# boiler.net
KiCad netlist of a schematic drawn in EAGLE
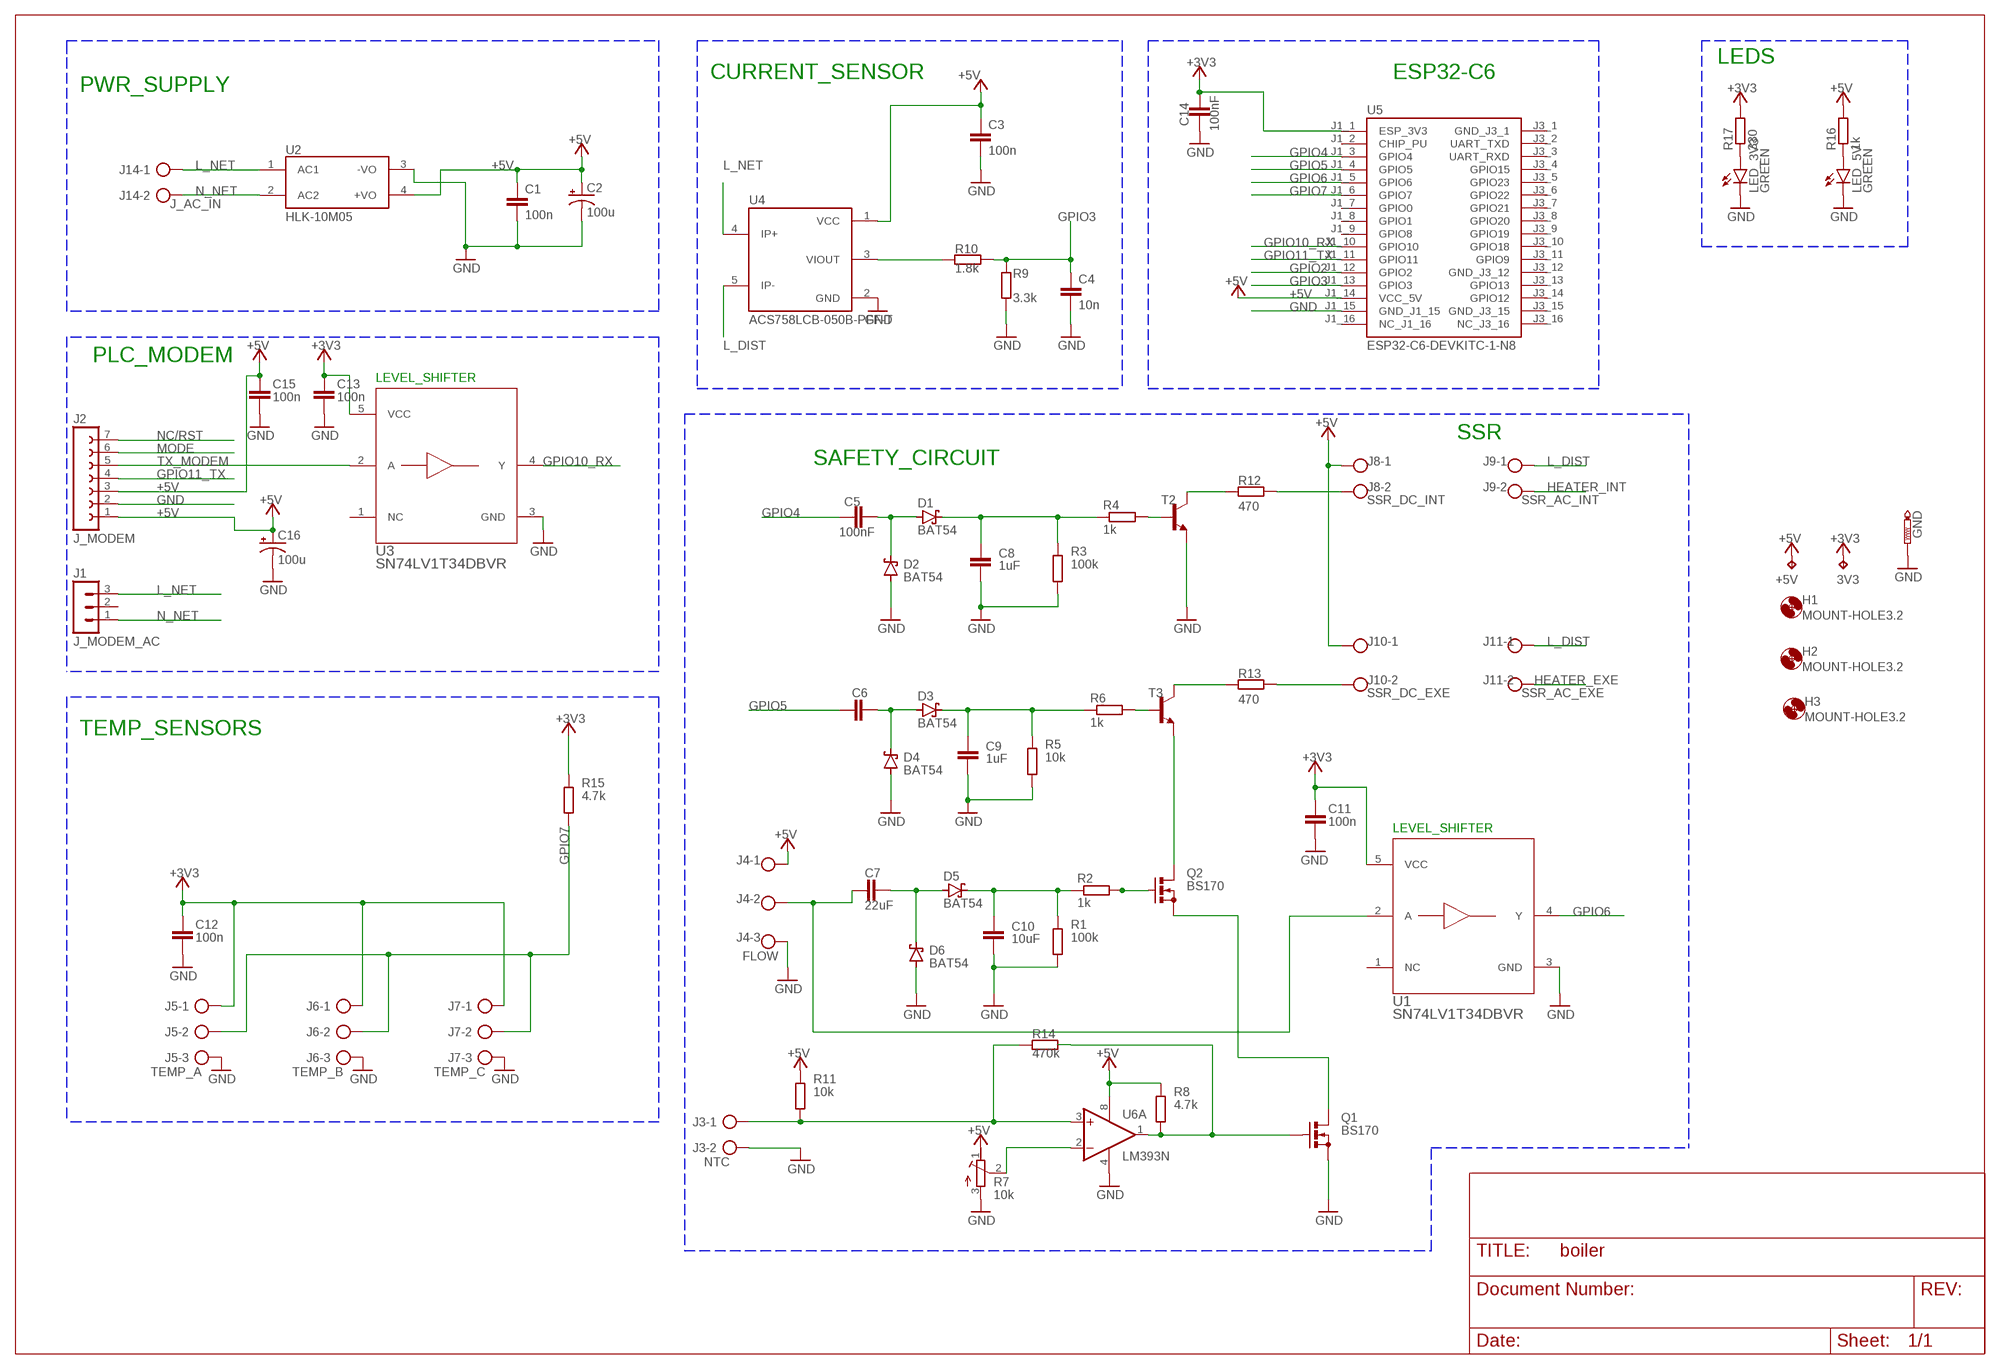
[diagram p0: schematic, sheet 1]

(export (version "E")
  (design (tool "Eeschema 10.0.6"))
  (components
    (comp (ref "+5V")
      (value "TPB2,54")
      (footprint "eagle-import:B2,54")
      (libsource (lib "eagle-import") (part "TPB2,54"))
    )
    (comp (ref "3V3")
      (value "TPB2,54")
      (footprint "eagle-import:B2,54")
      (libsource (lib "eagle-import") (part "TPB2,54"))
    )
    (comp (ref "C1")
      (value "100n")
      (footprint "eagle-import:C0603")
      (libsource (lib "eagle-import") (part "C-EUC0603"))
    )
    (comp (ref "C2")
      (value "100u")
      (footprint "eagle-import:PANASONIC_C")
      (libsource (lib "eagle-import") (part "CPOL-USC"))
    )
    (comp (ref "C3")
      (value "100n")
      (footprint "eagle-import:C0603")
      (libsource (lib "eagle-import") (part "C-EUC0603"))
    )
    (comp (ref "C4")
      (value "10n")
      (footprint "eagle-import:C0603")
      (libsource (lib "eagle-import") (part "C-EUC0603"))
    )
    (comp (ref "C5")
      (value "100nF")
      (footprint "eagle-import:C0603")
      (libsource (lib "eagle-import") (part "C-EUC0603"))
    )
    (comp (ref "C6")
      (value "1u")
      (footprint "eagle-import:C0603")
      (libsource (lib "eagle-import") (part "C-EUC0603"))
    )
    (comp (ref "C7")
      (value "22uF")
      (footprint "eagle-import:C0603")
      (libsource (lib "eagle-import") (part "C-EUC0603"))
    )
    (comp (ref "C8")
      (value "1uF")
      (footprint "eagle-import:C0603")
      (libsource (lib "eagle-import") (part "C-EUC0603"))
    )
    (comp (ref "C9")
      (value "1uF")
      (footprint "eagle-import:C0603")
      (libsource (lib "eagle-import") (part "C-EUC0603"))
    )
    (comp (ref "C10")
      (value "10uF")
      (footprint "eagle-import:C0603")
      (libsource (lib "eagle-import") (part "C-EUC0603"))
    )
    (comp (ref "C11")
      (value "100n")
      (footprint "eagle-import:C0603")
      (libsource (lib "eagle-import") (part "C-EUC0603"))
    )
    (comp (ref "C12")
      (value "100n")
      (footprint "eagle-import:C0603")
      (libsource (lib "eagle-import") (part "C-EUC0603"))
    )
    (comp (ref "C13")
      (value "100n")
      (footprint "eagle-import:C0603")
      (libsource (lib "eagle-import") (part "C-EUC0603"))
    )
    (comp (ref "C14")
      (value "100nF")
      (footprint "eagle-import:C0603")
      (libsource (lib "eagle-import") (part "C-EUC0603"))
    )
    (comp (ref "C15")
      (value "100n")
      (footprint "eagle-import:C0603")
      (libsource (lib "eagle-import") (part "C-EUC0603"))
    )
    (comp (ref "C16")
      (value "100u")
      (footprint "eagle-import:PANASONIC_C")
      (libsource (lib "eagle-import") (part "CPOL-USC"))
    )
    (comp (ref "D1")
      (value "BAT54")
      (footprint "eagle-import:SOT23")
      (libsource (lib "eagle-import") (part "BAT54"))
    )
    (comp (ref "D2")
      (value "BAT54")
      (footprint "eagle-import:SOT23")
      (libsource (lib "eagle-import") (part "BAT54"))
    )
    (comp (ref "D3")
      (value "BAT54")
      (footprint "eagle-import:SOT23")
      (libsource (lib "eagle-import") (part "BAT54"))
    )
    (comp (ref "D4")
      (value "BAT54")
      (footprint "eagle-import:SOT23")
      (libsource (lib "eagle-import") (part "BAT54"))
    )
    (comp (ref "D5")
      (value "BAT54")
      (footprint "eagle-import:SOT23")
      (libsource (lib "eagle-import") (part "BAT54"))
    )
    (comp (ref "D6")
      (value "BAT54")
      (footprint "eagle-import:SOT23")
      (libsource (lib "eagle-import") (part "BAT54"))
    )
    (comp (ref "GND")
      (value "PTR1TP15R")
      (footprint "eagle-import:TP15R")
      (libsource (lib "eagle-import") (part "PTR1TP15R"))
    )
    (comp (ref "H1")
      (value "MOUNT-HOLE3.2")
      (footprint "eagle-import:3,2")
      (libsource (lib "eagle-import") (part "MOUNT-HOLE3.2"))
    )
    (comp (ref "H2")
      (value "MOUNT-HOLE3.2")
      (footprint "eagle-import:3,2")
      (libsource (lib "eagle-import") (part "MOUNT-HOLE3.2"))
    )
    (comp (ref "H3")
      (value "MOUNT-HOLE3.2")
      (footprint "eagle-import:3,2")
      (libsource (lib "eagle-import") (part "MOUNT-HOLE3.2"))
    )
    (comp (ref "J1")
      (value "J_MODEM_AC")
      (footprint "eagle-import:MA03-1")
      (libsource (lib "eagle-import") (part "MA03-1"))
    )
    (comp (ref "J2")
      (value "J_MODEM")
      (footprint "eagle-import:FE07")
      (libsource (lib "eagle-import") (part "FE07-1"))
    )
    (comp (ref "J3")
      (value "NTC")
      (footprint "eagle-import:AK500_2")
      (libsource (lib "eagle-import") (part "AK500/2"))
    )
    (comp (ref "J4")
      (value "FLOW")
      (footprint "eagle-import:AK500_3")
      (libsource (lib "eagle-import") (part "AK500/3"))
    )
    (comp (ref "J5")
      (value "TEMP_A")
      (footprint "eagle-import:AK500_3")
      (libsource (lib "eagle-import") (part "AK500/3"))
    )
    (comp (ref "J6")
      (value "TEMP_B")
      (footprint "eagle-import:AK500_3")
      (libsource (lib "eagle-import") (part "AK500/3"))
    )
    (comp (ref "J7")
      (value "TEMP_C")
      (footprint "eagle-import:AK500_3")
      (libsource (lib "eagle-import") (part "AK500/3"))
    )
    (comp (ref "J8")
      (value "SSR_DC_INT")
      (footprint "eagle-import:AK500_2")
      (libsource (lib "eagle-import") (part "AK500/2"))
    )
    (comp (ref "J9")
      (value "SSR_AC_INT")
      (footprint "eagle-import:AK500_2")
      (libsource (lib "eagle-import") (part "AK500/2"))
    )
    (comp (ref "J10")
      (value "SSR_DC_EXE")
      (footprint "eagle-import:AK500_2")
      (libsource (lib "eagle-import") (part "AK500/2"))
    )
    (comp (ref "J11")
      (value "SSR_AC_EXE")
      (footprint "eagle-import:AK500_2")
      (libsource (lib "eagle-import") (part "AK500/2"))
    )
    (comp (ref "J14")
      (value "J_AC_IN")
      (footprint "eagle-import:AK500_2")
      (libsource (lib "eagle-import") (part "AK500/2"))
    )
    (comp (ref "LED_3V3")
      (value "GREEN")
      (footprint "eagle-import:CHIPLED_0603")
      (libsource (lib "eagle-import") (part "LEDCHIPLED_0603"))
    )
    (comp (ref "LED_5V")
      (value "GREEN")
      (footprint "eagle-import:CHIPLED_0603")
      (libsource (lib "eagle-import") (part "LEDCHIPLED_0603"))
    )
    (comp (ref "Q1")
      (value "BS170")
      (footprint "eagle-import:SOT54E")
      (libsource (lib "eagle-import") (part "BS170"))
    )
    (comp (ref "Q2")
      (value "BS170")
      (footprint "eagle-import:SOT54E")
      (libsource (lib "eagle-import") (part "BS170"))
    )
    (comp (ref "R1")
      (value "100k")
      (footprint "eagle-import:R0603")
      (libsource (lib "eagle-import") (part "R-EU_R0603"))
    )
    (comp (ref "R2")
      (value "1k")
      (footprint "eagle-import:R0603")
      (libsource (lib "eagle-import") (part "R-EU_R0603"))
    )
    (comp (ref "R3")
      (value "100k")
      (footprint "eagle-import:R0603")
      (libsource (lib "eagle-import") (part "R-EU_R0603"))
    )
    (comp (ref "R4")
      (value "1k")
      (footprint "eagle-import:R0603")
      (libsource (lib "eagle-import") (part "R-EU_R0603"))
    )
    (comp (ref "R5")
      (value "10k")
      (footprint "eagle-import:R0603")
      (libsource (lib "eagle-import") (part "R-EU_R0603"))
    )
    (comp (ref "R6")
      (value "1k")
      (footprint "eagle-import:R0603")
      (libsource (lib "eagle-import") (part "R-EU_R0603"))
    )
    (comp (ref "R7")
      (value "10k")
      (footprint "eagle-import:RTRIM3314G")
      (libsource (lib "eagle-import") (part "R-TRIMM3314G"))
    )
    (comp (ref "R8")
      (value "4.7k")
      (footprint "eagle-import:R0603")
      (libsource (lib "eagle-import") (part "R-EU_R0603"))
    )
    (comp (ref "R9")
      (value "3.3k")
      (footprint "eagle-import:R0603")
      (libsource (lib "eagle-import") (part "R-EU_R0603"))
    )
    (comp (ref "R10")
      (value "1.8k")
      (footprint "eagle-import:R0603")
      (libsource (lib "eagle-import") (part "R-EU_R0603"))
    )
    (comp (ref "R11")
      (value "10k")
      (footprint "eagle-import:R0603")
      (libsource (lib "eagle-import") (part "R-EU_R0603"))
    )
    (comp (ref "R12")
      (value "470")
      (footprint "eagle-import:R0603")
      (libsource (lib "eagle-import") (part "R-EU_R0603"))
    )
    (comp (ref "R13")
      (value "470")
      (footprint "eagle-import:R0603")
      (libsource (lib "eagle-import") (part "R-EU_R0603"))
    )
    (comp (ref "R14")
      (value "470k")
      (footprint "eagle-import:R0603")
      (libsource (lib "eagle-import") (part "R-EU_R0603"))
    )
    (comp (ref "R15")
      (value "4.7k")
      (footprint "eagle-import:R0603")
      (libsource (lib "eagle-import") (part "R-EU_R0603"))
    )
    (comp (ref "R16")
      (value "1k")
      (footprint "eagle-import:R0603")
      (libsource (lib "eagle-import") (part "R-EU_R0603"))
    )
    (comp (ref "R17")
      (value "330")
      (footprint "eagle-import:R0603")
      (libsource (lib "eagle-import") (part "R-EU_R0603"))
    )
    (comp (ref "T2")
      (value "2N2222-NPN-TO92-EBC")
      (footprint "eagle-import:TO92-EBC")
      (libsource (lib "eagle-import") (part "-NPN-TO92-EBC2N2222"))
    )
    (comp (ref "T3")
      (value "2N2222-NPN-TO92-EBC")
      (footprint "eagle-import:TO92-EBC")
      (libsource (lib "eagle-import") (part "-NPN-TO92-EBC2N2222"))
    )
    (comp (ref "U1")
      (value "SN74LV1T34DBVR")
      (footprint "eagle-import:DBV0005A_N")
      (fields (field (name "COPYRIGHT") "Copyright (C) 2026 Ultra Librarian. All rights reserved."))
      (libsource (lib "eagle-import") (part "SN74LV1T34DBVR"))
    )
    (comp (ref "U2")
      (value "HLK-10M05")
      (footprint "eagle-import:CONV_HLK-10M05")
      (fields (field (name "MF") "Hi-link"))
      (libsource (lib "eagle-import") (part "HLK-10M05"))
    )
    (comp (ref "U3")
      (value "SN74LV1T34DBVR")
      (footprint "eagle-import:DBV0005A_N")
      (fields (field (name "COPYRIGHT") "Copyright (C) 2026 Ultra Librarian. All rights reserved."))
      (libsource (lib "eagle-import") (part "SN74LV1T34DBVR"))
    )
    (comp (ref "U4")
      (value "ACS758LCB-050B-PFF-T")
      (footprint "eagle-import:XDCR_ACS758LCB-050B-PFF-T")
      (fields (field (name "MF") "Allegro MicroSystems LLC"))
      (libsource (lib "eagle-import") (part "ACS758LCB-050B-PFF-T"))
    )
    (comp (ref "U5")
      (value "ESP32-C6-DEVKITC-1-N8")
      (footprint "eagle-import:MODULE_ESP32-C6-DEVKITC-1-N8")
      (fields (field (name "MANUFACTURER") "Espressif Systems"))
      (libsource (lib "eagle-import") (part "ESP32-C6-DEVKITC-1-N8"))
    )
    (comp (ref "U6")
      (value "LM393N")
      (footprint "eagle-import:DIL08")
      (libsource (lib "eagle-import") (part "LM393N"))
    )
  )
  (nets
    (net (code "1") (name "+3V3") (class "Default")
      (node (ref "3V3") (pin "TP") (pinfunction "TP_TP") (pintype "input"))
      (node (ref "C11") (pin "2") (pinfunction "2_2") (pintype "passive"))
      (node (ref "C12") (pin "2") (pinfunction "2_2") (pintype "passive"))
      (node (ref "C13") (pin "2") (pinfunction "2_2") (pintype "passive"))
      (node (ref "C14") (pin "2") (pinfunction "2_2") (pintype "passive"))
      (node (ref "J5") (pin "1") (pinfunction "KL_1") (pintype "passive"))
      (node (ref "J6") (pin "1") (pinfunction "KL_1") (pintype "passive"))
      (node (ref "J7") (pin "1") (pinfunction "KL_1") (pintype "passive"))
      (node (ref "R15") (pin "2") (pinfunction "2_2") (pintype "passive"))
      (node (ref "R17") (pin "2") (pinfunction "2_2") (pintype "passive"))
      (node (ref "U1") (pin "5") (pinfunction "VCC_5") (pintype "power_in"))
      (node (ref "U3") (pin "5") (pinfunction "VCC_5") (pintype "power_in"))
      (node (ref "U5") (pin "J1_1") (pinfunction "ESP_3V3_J1_1") (pintype "power_in"))
    )
    (net (code "2") (name "+5V") (class "Default")
      (node (ref "+5V") (pin "TP") (pinfunction "TP_TP") (pintype "input"))
      (node (ref "C1") (pin "2") (pinfunction "2_2") (pintype "passive"))
      (node (ref "C15") (pin "2") (pinfunction "2_2") (pintype "passive"))
      (node (ref "C16") (pin "+") (pinfunction "+_+") (pintype "passive"))
      (node (ref "C2") (pin "+") (pinfunction "+_+") (pintype "passive"))
      (node (ref "C3") (pin "1") (pinfunction "1_1") (pintype "passive"))
      (node (ref "J10") (pin "1") (pinfunction "KL_1") (pintype "passive"))
      (node (ref "J2") (pin "1") (pinfunction "1_1") (pintype "passive"))
      (node (ref "J2") (pin "3") (pinfunction "3_3") (pintype "passive"))
      (node (ref "J4") (pin "1") (pinfunction "KL_1") (pintype "passive"))
      (node (ref "J8") (pin "1") (pinfunction "KL_1") (pintype "passive"))
      (node (ref "R11") (pin "2") (pinfunction "2_2") (pintype "passive"))
      (node (ref "R16") (pin "2") (pinfunction "2_2") (pintype "passive"))
      (node (ref "R7") (pin "1") (pinfunction "E_1") (pintype "passive"))
      (node (ref "R8") (pin "2") (pinfunction "2_2") (pintype "passive"))
      (node (ref "U2") (pin "4") (pinfunction "+VO_4") (pintype "output"))
      (node (ref "U4") (pin "1") (pinfunction "VCC_1") (pintype "power_in"))
      (node (ref "U5") (pin "J1_14") (pinfunction "VCC_5V_J1_14") (pintype "power_in"))
      (node (ref "U6") (pin "8") (pinfunction "V+_8") (pintype "power_in"))
    )
    (net (code "3") (name "/GND_J3_1") (class "Default")
      (node (ref "U5") (pin "J3_1") (pinfunction "GND_J3_1_J3_1") (pintype "power_in"))
    )
    (net (code "4") (name "/GND_J3_12") (class "Default")
      (node (ref "U5") (pin "J3_12") (pinfunction "GND_J3_12_J3_12") (pintype "power_in"))
    )
    (net (code "5") (name "/GND_J3_15") (class "Default")
      (node (ref "U5") (pin "J3_15") (pinfunction "GND_J3_15_J3_15") (pintype "power_in"))
    )
    (net (code "6") (name "/GPIO2") (class "Default")
      (node (ref "U5") (pin "J1_12") (pinfunction "GPIO2_J1_12") (pintype "bidirectional"))
    )
    (net (code "7") (name "/GPIO3") (class "Default")
      (node (ref "C4") (pin "1") (pinfunction "1_1") (pintype "passive"))
      (node (ref "R10") (pin "1") (pinfunction "1_1") (pintype "passive"))
      (node (ref "R9") (pin "2") (pinfunction "2_2") (pintype "passive"))
      (node (ref "U5") (pin "J1_13") (pinfunction "GPIO3_J1_13") (pintype "bidirectional"))
    )
    (net (code "8") (name "/GPIO4") (class "Default")
      (node (ref "C5") (pin "1") (pinfunction "1_1") (pintype "passive"))
      (node (ref "U5") (pin "J1_3") (pinfunction "GPIO4_J1_3") (pintype "bidirectional"))
    )
    (net (code "9") (name "/GPIO5") (class "Default")
      (node (ref "C6") (pin "1") (pinfunction "1_1") (pintype "passive"))
      (node (ref "U5") (pin "J1_4") (pinfunction "GPIO5_J1_4") (pintype "bidirectional"))
    )
    (net (code "10") (name "/GPIO6") (class "Default")
      (node (ref "U1") (pin "4") (pinfunction "Y_4") (pintype "output"))
      (node (ref "U5") (pin "J1_5") (pinfunction "GPIO6_J1_5") (pintype "bidirectional"))
    )
    (net (code "11") (name "/GPIO7") (class "Default")
      (node (ref "J5") (pin "2") (pinfunction "KL_2") (pintype "passive"))
      (node (ref "J6") (pin "2") (pinfunction "KL_2") (pintype "passive"))
      (node (ref "J7") (pin "2") (pinfunction "KL_2") (pintype "passive"))
      (node (ref "R15") (pin "1") (pinfunction "1_1") (pintype "passive"))
      (node (ref "U5") (pin "J1_6") (pinfunction "GPIO7_J1_6") (pintype "bidirectional"))
    )
    (net (code "12") (name "/GPIO10_RX") (class "Default")
      (node (ref "U3") (pin "4") (pinfunction "Y_4") (pintype "output"))
      (node (ref "U5") (pin "J1_10") (pinfunction "GPIO10_J1_10") (pintype "bidirectional"))
    )
    (net (code "13") (name "/GPIO11_TX") (class "Default")
      (node (ref "J2") (pin "4") (pinfunction "4_4") (pintype "passive"))
      (node (ref "U5") (pin "J1_11") (pinfunction "GPIO11_J1_11") (pintype "bidirectional"))
    )
    (net (code "14") (name "/HEATER_EXE") (class "Default")
      (node (ref "J11") (pin "2") (pinfunction "KL_2") (pintype "passive"))
    )
    (net (code "15") (name "/HEATER_INT") (class "Default")
      (node (ref "J9") (pin "2") (pinfunction "KL_2") (pintype "passive"))
    )
    (net (code "16") (name "/L_DIST") (class "Default")
      (node (ref "J11") (pin "1") (pinfunction "KL_1") (pintype "passive"))
      (node (ref "J9") (pin "1") (pinfunction "KL_1") (pintype "passive"))
      (node (ref "U4") (pin "5") (pinfunction "IP-_5") (pintype "input"))
    )
    (net (code "17") (name "/L_NET") (class "Default")
      (node (ref "J1") (pin "3") (pinfunction "3_3") (pintype "passive"))
      (node (ref "J14") (pin "1") (pinfunction "KL_1") (pintype "passive"))
      (node (ref "U2") (pin "1") (pinfunction "AC1_1") (pintype "input"))
      (node (ref "U4") (pin "4") (pinfunction "IP+_4") (pintype "input"))
    )
    (net (code "18") (name "/MODE") (class "Default")
      (node (ref "J2") (pin "6") (pinfunction "6_6") (pintype "passive"))
    )
    (net (code "19") (name "/NC{slash}RST") (class "Default")
      (node (ref "J2") (pin "7") (pinfunction "7_7") (pintype "passive"))
    )
    (net (code "20") (name "/N_NET") (class "Default")
      (node (ref "J1") (pin "1") (pinfunction "1_1") (pintype "passive"))
      (node (ref "J14") (pin "2") (pinfunction "KL_2") (pintype "passive"))
      (node (ref "U2") (pin "2") (pinfunction "AC2_2") (pintype "input"))
    )
    (net (code "21") (name "/TX_MODEM") (class "Default")
      (node (ref "J2") (pin "5") (pinfunction "5_5") (pintype "passive"))
      (node (ref "U3") (pin "2") (pinfunction "A_2") (pintype "input"))
    )
    (net (code "22") (name "GND") (class "Default")
      (node (ref "C1") (pin "1") (pinfunction "1_1") (pintype "passive"))
      (node (ref "C10") (pin "2") (pinfunction "2_2") (pintype "passive"))
      (node (ref "C11") (pin "1") (pinfunction "1_1") (pintype "passive"))
      (node (ref "C12") (pin "1") (pinfunction "1_1") (pintype "passive"))
      (node (ref "C13") (pin "1") (pinfunction "1_1") (pintype "passive"))
      (node (ref "C14") (pin "1") (pinfunction "1_1") (pintype "passive"))
      (node (ref "C15") (pin "1") (pinfunction "1_1") (pintype "passive"))
      (node (ref "C16") (pin "-") (pinfunction "-_-") (pintype "passive"))
      (node (ref "C2") (pin "-") (pinfunction "-_-") (pintype "passive"))
      (node (ref "C3") (pin "2") (pinfunction "2_2") (pintype "passive"))
      (node (ref "C4") (pin "2") (pinfunction "2_2") (pintype "passive"))
      (node (ref "C8") (pin "2") (pinfunction "2_2") (pintype "passive"))
      (node (ref "C9") (pin "2") (pinfunction "2_2") (pintype "passive"))
      (node (ref "D2") (pin "1") (pinfunction "A_1") (pintype "passive"))
      (node (ref "D4") (pin "1") (pinfunction "A_1") (pintype "passive"))
      (node (ref "D6") (pin "1") (pinfunction "A_1") (pintype "passive"))
      (node (ref "GND") (pin "TP") (pinfunction "TP_TP") (pintype "input"))
      (node (ref "J2") (pin "2") (pinfunction "2_2") (pintype "passive"))
      (node (ref "J3") (pin "2") (pinfunction "KL_2") (pintype "passive"))
      (node (ref "J4") (pin "3") (pinfunction "KL_3") (pintype "passive"))
      (node (ref "J5") (pin "3") (pinfunction "KL_3") (pintype "passive"))
      (node (ref "J6") (pin "3") (pinfunction "KL_3") (pintype "passive"))
      (node (ref "J7") (pin "3") (pinfunction "KL_3") (pintype "passive"))
      (node (ref "LED_3V3") (pin "C") (pinfunction "C_C") (pintype "passive"))
      (node (ref "LED_5V") (pin "C") (pinfunction "C_C") (pintype "passive"))
      (node (ref "Q1") (pin "S") (pinfunction "S_S") (pintype "passive"))
      (node (ref "R1") (pin "1") (pinfunction "1_1") (pintype "passive"))
      (node (ref "R3") (pin "1") (pinfunction "1_1") (pintype "passive"))
      (node (ref "R5") (pin "1") (pinfunction "1_1") (pintype "passive"))
      (node (ref "R7") (pin "3") (pinfunction "A_3") (pintype "passive"))
      (node (ref "R9") (pin "1") (pinfunction "1_1") (pintype "passive"))
      (node (ref "T2") (pin "E") (pinfunction "E_E") (pintype "passive"))
      (node (ref "U1") (pin "3") (pinfunction "GND_3") (pintype "power_in"))
      (node (ref "U2") (pin "3") (pinfunction "-VO_3") (pintype "output"))
      (node (ref "U3") (pin "3") (pinfunction "GND_3") (pintype "power_in"))
      (node (ref "U4") (pin "2") (pinfunction "GND_2") (pintype "power_in"))
      (node (ref "U5") (pin "J1_15") (pinfunction "GND_J1_15_J1_15") (pintype "power_in"))
      (node (ref "U6") (pin "4") (pinfunction "V-_4") (pintype "power_in"))
    )
    (net (code "23") (name "Net-(D1-A)") (class "Default")
      (node (ref "C5") (pin "2") (pinfunction "2_2") (pintype "passive"))
      (node (ref "D1") (pin "1") (pinfunction "A_1") (pintype "passive"))
      (node (ref "D2") (pin "3") (pinfunction "C_3") (pintype "passive"))
    )
    (net (code "24") (name "Net-(D1-C)") (class "Default")
      (node (ref "C8") (pin "1") (pinfunction "1_1") (pintype "passive"))
      (node (ref "D1") (pin "3") (pinfunction "C_3") (pintype "passive"))
      (node (ref "R3") (pin "2") (pinfunction "2_2") (pintype "passive"))
      (node (ref "R4") (pin "1") (pinfunction "1_1") (pintype "passive"))
    )
    (net (code "25") (name "Net-(D3-A)") (class "Default")
      (node (ref "C6") (pin "2") (pinfunction "2_2") (pintype "passive"))
      (node (ref "D3") (pin "1") (pinfunction "A_1") (pintype "passive"))
      (node (ref "D4") (pin "3") (pinfunction "C_3") (pintype "passive"))
    )
    (net (code "26") (name "Net-(D3-C)") (class "Default")
      (node (ref "C9") (pin "1") (pinfunction "1_1") (pintype "passive"))
      (node (ref "D3") (pin "3") (pinfunction "C_3") (pintype "passive"))
      (node (ref "R5") (pin "2") (pinfunction "2_2") (pintype "passive"))
      (node (ref "R6") (pin "1") (pinfunction "1_1") (pintype "passive"))
    )
    (net (code "27") (name "Net-(D5-A)") (class "Default")
      (node (ref "C7") (pin "2") (pinfunction "2_2") (pintype "passive"))
      (node (ref "D5") (pin "1") (pinfunction "A_1") (pintype "passive"))
      (node (ref "D6") (pin "3") (pinfunction "C_3") (pintype "passive"))
    )
    (net (code "28") (name "Net-(D5-C)") (class "Default")
      (node (ref "C10") (pin "1") (pinfunction "1_1") (pintype "passive"))
      (node (ref "D5") (pin "3") (pinfunction "C_3") (pintype "passive"))
      (node (ref "R1") (pin "2") (pinfunction "2_2") (pintype "passive"))
      (node (ref "R2") (pin "1") (pinfunction "1_1") (pintype "passive"))
    )
    (net (code "29") (name "Net-(J3A-KL)") (class "Default")
      (node (ref "J3") (pin "1") (pinfunction "KL_1") (pintype "passive"))
      (node (ref "R11") (pin "1") (pinfunction "1_1") (pintype "passive"))
      (node (ref "R14") (pin "2") (pinfunction "2_2") (pintype "passive"))
      (node (ref "U6") (pin "3") (pinfunction "+IN_3") (pintype "input"))
    )
    (net (code "30") (name "Net-(J4B-KL)") (class "Default")
      (node (ref "C7") (pin "1") (pinfunction "1_1") (pintype "passive"))
      (node (ref "J4") (pin "2") (pinfunction "KL_2") (pintype "passive"))
      (node (ref "U1") (pin "2") (pinfunction "A_2") (pintype "input"))
    )
    (net (code "31") (name "Net-(J8B-KL)") (class "Default")
      (node (ref "J8") (pin "2") (pinfunction "KL_2") (pintype "passive"))
      (node (ref "R12") (pin "1") (pinfunction "1_1") (pintype "passive"))
    )
    (net (code "32") (name "Net-(J10B-KL)") (class "Default")
      (node (ref "J10") (pin "2") (pinfunction "KL_2") (pintype "passive"))
      (node (ref "R13") (pin "1") (pinfunction "1_1") (pintype "passive"))
    )
    (net (code "33") (name "Net-(LED_3V3-PadA)") (class "Default")
      (node (ref "LED_3V3") (pin "A") (pinfunction "A_A") (pintype "passive"))
      (node (ref "R17") (pin "1") (pinfunction "1_1") (pintype "passive"))
    )
    (net (code "34") (name "Net-(LED_5V-PadA)") (class "Default")
      (node (ref "LED_5V") (pin "A") (pinfunction "A_A") (pintype "passive"))
      (node (ref "R16") (pin "1") (pinfunction "1_1") (pintype "passive"))
    )
    (net (code "35") (name "Net-(Q1-PadD)") (class "Default")
      (node (ref "Q1") (pin "D") (pinfunction "D_D") (pintype "passive"))
      (node (ref "Q2") (pin "S") (pinfunction "S_S") (pintype "passive"))
    )
    (net (code "36") (name "Net-(Q2-PadD)") (class "Default")
      (node (ref "Q2") (pin "D") (pinfunction "D_D") (pintype "passive"))
      (node (ref "T3") (pin "E") (pinfunction "E_E") (pintype "passive"))
    )
    (net (code "37") (name "Net-(Q2-PadG)") (class "Default")
      (node (ref "Q2") (pin "G") (pinfunction "G_G") (pintype "passive"))
      (node (ref "R2") (pin "2") (pinfunction "2_2") (pintype "passive"))
    )
    (net (code "38") (name "Net-(R4-Pad2)") (class "Default")
      (node (ref "R4") (pin "2") (pinfunction "2_2") (pintype "passive"))
      (node (ref "T2") (pin "B") (pinfunction "B_B") (pintype "passive"))
    )
    (net (code "39") (name "Net-(R6-Pad2)") (class "Default")
      (node (ref "R6") (pin "2") (pinfunction "2_2") (pintype "passive"))
      (node (ref "T3") (pin "B") (pinfunction "B_B") (pintype "passive"))
    )
    (net (code "40") (name "Net-(R7-S)") (class "Default")
      (node (ref "R7") (pin "2") (pinfunction "S_2") (pintype "passive"))
      (node (ref "U6") (pin "2") (pinfunction "-IN_2") (pintype "input"))
    )
    (net (code "41") (name "Net-(R12-Pad2)") (class "Default")
      (node (ref "R12") (pin "2") (pinfunction "2_2") (pintype "passive"))
      (node (ref "T2") (pin "C") (pinfunction "C_C") (pintype "passive"))
    )
    (net (code "42") (name "Net-(R13-Pad2)") (class "Default")
      (node (ref "R13") (pin "2") (pinfunction "2_2") (pintype "passive"))
      (node (ref "T3") (pin "C") (pinfunction "C_C") (pintype "passive"))
    )
    (net (code "43") (name "Net-(U4-VIOUT)") (class "Default")
      (node (ref "R10") (pin "2") (pinfunction "2_2") (pintype "passive"))
      (node (ref "U4") (pin "3") (pinfunction "VIOUT_3") (pintype "output"))
    )
    (net (code "44") (name "Net-(U6A-OUT)") (class "Default")
      (node (ref "Q1") (pin "G") (pinfunction "G_G") (pintype "passive"))
      (node (ref "R14") (pin "1") (pinfunction "1_1") (pintype "passive"))
      (node (ref "R8") (pin "1") (pinfunction "1_1") (pintype "passive"))
      (node (ref "U6") (pin "1") (pinfunction "OUT_1") (pintype "output"))
    )
    (net (code "45") (name "unconnected-(J1-Pad2)") (class "Default")
      (node (ref "J1") (pin "2") (pinfunction "2_2") (pintype "passive"))
    )
    (net (code "46") (name "unconnected-(U1-NC-Pad1)") (class "Default")
      (node (ref "U1") (pin "1") (pinfunction "NC_1") (pintype "passive"))
    )
    (net (code "47") (name "unconnected-(U3-NC-Pad1)") (class "Default")
      (node (ref "U3") (pin "1") (pinfunction "NC_1") (pintype "passive"))
    )
    (net (code "48") (name "unconnected-(U5-CHIP_PU-PadJ1_2)") (class "Default")
      (node (ref "U5") (pin "J1_2") (pinfunction "CHIP_PU_J1_2") (pintype "input"))
    )
    (net (code "49") (name "unconnected-(U5-GPIO0-PadJ1_7)") (class "Default")
      (node (ref "U5") (pin "J1_7") (pinfunction "GPIO0_J1_7") (pintype "bidirectional"))
    )
    (net (code "50") (name "unconnected-(U5-GPIO1-PadJ1_8)") (class "Default")
      (node (ref "U5") (pin "J1_8") (pinfunction "GPIO1_J1_8") (pintype "bidirectional"))
    )
    (net (code "51") (name "unconnected-(U5-GPIO8-PadJ1_9)") (class "Default")
      (node (ref "U5") (pin "J1_9") (pinfunction "GPIO8_J1_9") (pintype "bidirectional"))
    )
    (net (code "52") (name "unconnected-(U5-GPIO9-PadJ3_11)") (class "Default")
      (node (ref "U5") (pin "J3_11") (pinfunction "GPIO9_J3_11") (pintype "bidirectional"))
    )
    (net (code "53") (name "unconnected-(U5-GPIO12-PadJ3_14)") (class "Default")
      (node (ref "U5") (pin "J3_14") (pinfunction "GPIO12_J3_14") (pintype "bidirectional"))
    )
    (net (code "54") (name "unconnected-(U5-GPIO13-PadJ3_13)") (class "Default")
      (node (ref "U5") (pin "J3_13") (pinfunction "GPIO13_J3_13") (pintype "bidirectional"))
    )
    (net (code "55") (name "unconnected-(U5-GPIO15-PadJ3_4)") (class "Default")
      (node (ref "U5") (pin "J3_4") (pinfunction "GPIO15_J3_4") (pintype "bidirectional"))
    )
    (net (code "56") (name "unconnected-(U5-GPIO18-PadJ3_10)") (class "Default")
      (node (ref "U5") (pin "J3_10") (pinfunction "GPIO18_J3_10") (pintype "bidirectional"))
    )
    (net (code "57") (name "unconnected-(U5-GPIO19-PadJ3_9)") (class "Default")
      (node (ref "U5") (pin "J3_9") (pinfunction "GPIO19_J3_9") (pintype "bidirectional"))
    )
    (net (code "58") (name "unconnected-(U5-GPIO20-PadJ3_8)") (class "Default")
      (node (ref "U5") (pin "J3_8") (pinfunction "GPIO20_J3_8") (pintype "bidirectional"))
    )
    (net (code "59") (name "unconnected-(U5-GPIO21-PadJ3_7)") (class "Default")
      (node (ref "U5") (pin "J3_7") (pinfunction "GPIO21_J3_7") (pintype "bidirectional"))
    )
    (net (code "60") (name "unconnected-(U5-GPIO22-PadJ3_6)") (class "Default")
      (node (ref "U5") (pin "J3_6") (pinfunction "GPIO22_J3_6") (pintype "bidirectional"))
    )
    (net (code "61") (name "unconnected-(U5-GPIO23-PadJ3_5)") (class "Default")
      (node (ref "U5") (pin "J3_5") (pinfunction "GPIO23_J3_5") (pintype "bidirectional"))
    )
    (net (code "62") (name "unconnected-(U5-NC_J1_16-PadJ1_16)") (class "Default")
      (node (ref "U5") (pin "J1_16") (pinfunction "NC_J1_16_J1_16") (pintype "no_connect"))
    )
    (net (code "63") (name "unconnected-(U5-NC_J3_16-PadJ3_16)") (class "Default")
      (node (ref "U5") (pin "J3_16") (pinfunction "NC_J3_16_J3_16") (pintype "no_connect"))
    )
    (net (code "64") (name "unconnected-(U5-UART_RXD-PadJ3_3)") (class "Default")
      (node (ref "U5") (pin "J3_3") (pinfunction "UART_RXD_J3_3") (pintype "bidirectional"))
    )
    (net (code "65") (name "unconnected-(U5-UART_TXD-PadJ3_2)") (class "Default")
      (node (ref "U5") (pin "J3_2") (pinfunction "UART_TXD_J3_2") (pintype "bidirectional"))
    )
  )
)
